# ADS1298.net
KiCad netlist of a schematic drawn in Altium Designer
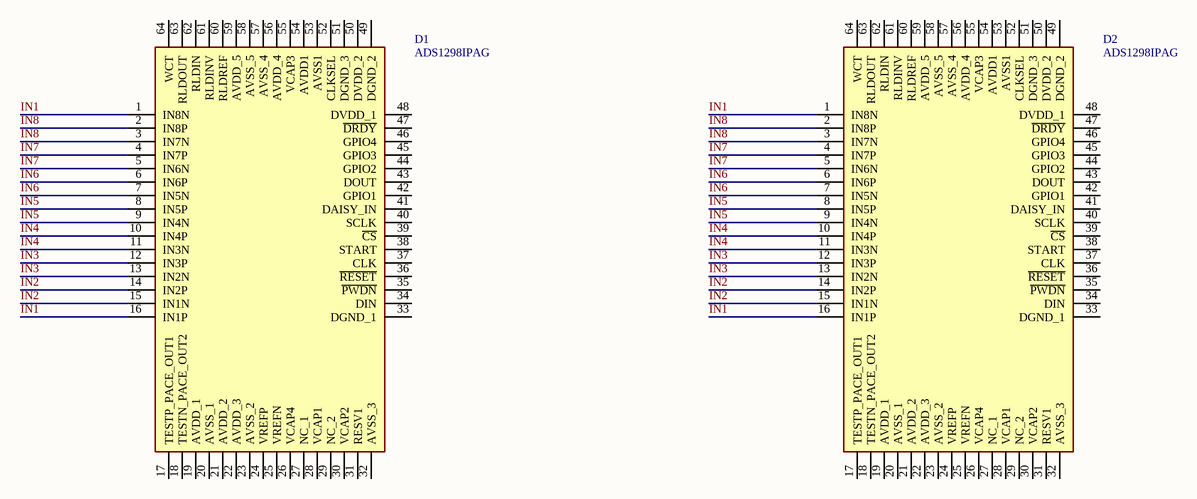
[diagram p0: ADS1298.SchDoc]

(export (version "E")
  (design (tool "Eeschema 10.0.6"))
  (components
    (comp (ref "D1")
      (value "ADS1298IPAG")
      (footprint "pcb_lib:QFP50P1200X1200X120-64N")
      (description "Integrated Circuit")
      (fields (field (name "MOUSER PART NUMBER") "595-ADS1298IPAG"))
      (libsource (lib "*") (part "ADS1298IPAG"))
    )
    (comp (ref "D2")
      (value "ADS1298IPAG")
      (footprint "pcb_lib:QFP50P1200X1200X120-64N")
      (description "Integrated Circuit")
      (fields (field (name "MOUSER PART NUMBER") "595-ADS1298IPAG"))
      (libsource (lib "*") (part "ADS1298IPAG"))
    )
  )
  (nets
    (net (code "1") (name "/IN1") (class "Default")
      (node (ref "D1") (pin "1") (pinfunction "IN8N_1") (pintype "passive"))
      (node (ref "D1") (pin "16") (pinfunction "IN1P_16") (pintype "passive"))
      (node (ref "D2") (pin "1") (pinfunction "IN8N_1") (pintype "passive"))
      (node (ref "D2") (pin "16") (pinfunction "IN1P_16") (pintype "passive"))
    )
    (net (code "2") (name "/IN2") (class "Default")
      (node (ref "D1") (pin "14") (pinfunction "IN2P_14") (pintype "passive"))
      (node (ref "D1") (pin "15") (pinfunction "IN1N_15") (pintype "passive"))
      (node (ref "D2") (pin "14") (pinfunction "IN2P_14") (pintype "passive"))
      (node (ref "D2") (pin "15") (pinfunction "IN1N_15") (pintype "passive"))
    )
    (net (code "3") (name "/IN3") (class "Default")
      (node (ref "D1") (pin "12") (pinfunction "IN3P_12") (pintype "passive"))
      (node (ref "D1") (pin "13") (pinfunction "IN2N_13") (pintype "passive"))
      (node (ref "D2") (pin "12") (pinfunction "IN3P_12") (pintype "passive"))
      (node (ref "D2") (pin "13") (pinfunction "IN2N_13") (pintype "passive"))
    )
    (net (code "4") (name "/IN4") (class "Default")
      (node (ref "D1") (pin "10") (pinfunction "IN4P_10") (pintype "passive"))
      (node (ref "D1") (pin "11") (pinfunction "IN3N_11") (pintype "passive"))
      (node (ref "D2") (pin "10") (pinfunction "IN4P_10") (pintype "passive"))
      (node (ref "D2") (pin "11") (pinfunction "IN3N_11") (pintype "passive"))
    )
    (net (code "5") (name "/IN5") (class "Default")
      (node (ref "D1") (pin "8") (pinfunction "IN5P_8") (pintype "passive"))
      (node (ref "D1") (pin "9") (pinfunction "IN4N_9") (pintype "passive"))
      (node (ref "D2") (pin "8") (pinfunction "IN5P_8") (pintype "passive"))
      (node (ref "D2") (pin "9") (pinfunction "IN4N_9") (pintype "passive"))
    )
    (net (code "6") (name "/IN6") (class "Default")
      (node (ref "D1") (pin "6") (pinfunction "IN6P_6") (pintype "passive"))
      (node (ref "D1") (pin "7") (pinfunction "IN5N_7") (pintype "passive"))
      (node (ref "D2") (pin "6") (pinfunction "IN6P_6") (pintype "passive"))
      (node (ref "D2") (pin "7") (pinfunction "IN5N_7") (pintype "passive"))
    )
    (net (code "7") (name "/IN7") (class "Default")
      (node (ref "D1") (pin "4") (pinfunction "IN7P_4") (pintype "passive"))
      (node (ref "D1") (pin "5") (pinfunction "IN6N_5") (pintype "passive"))
      (node (ref "D2") (pin "4") (pinfunction "IN7P_4") (pintype "passive"))
      (node (ref "D2") (pin "5") (pinfunction "IN6N_5") (pintype "passive"))
    )
    (net (code "8") (name "/IN8") (class "Default")
      (node (ref "D1") (pin "2") (pinfunction "IN8P_2") (pintype "passive"))
      (node (ref "D1") (pin "3") (pinfunction "IN7N_3") (pintype "passive"))
      (node (ref "D2") (pin "2") (pinfunction "IN8P_2") (pintype "passive"))
      (node (ref "D2") (pin "3") (pinfunction "IN7N_3") (pintype "passive"))
    )
    (net (code "9") (name "unconnected-(D1-AVDD1-Pad54)") (class "Default")
      (node (ref "D1") (pin "54") (pinfunction "AVDD1_54") (pintype "passive"))
    )
    (net (code "10") (name "unconnected-(D1-AVDD_1-Pad19)") (class "Default")
      (node (ref "D1") (pin "19") (pinfunction "AVDD_1_19") (pintype "passive"))
    )
    (net (code "11") (name "unconnected-(D1-AVDD_2-Pad21)") (class "Default")
      (node (ref "D1") (pin "21") (pinfunction "AVDD_2_21") (pintype "passive"))
    )
    (net (code "12") (name "unconnected-(D1-AVDD_3-Pad22)") (class "Default")
      (node (ref "D1") (pin "22") (pinfunction "AVDD_3_22") (pintype "passive"))
    )
    (net (code "13") (name "unconnected-(D1-AVDD_4-Pad56)") (class "Default")
      (node (ref "D1") (pin "56") (pinfunction "AVDD_4_56") (pintype "passive"))
    )
    (net (code "14") (name "unconnected-(D1-AVDD_5-Pad59)") (class "Default")
      (node (ref "D1") (pin "59") (pinfunction "AVDD_5_59") (pintype "passive"))
    )
    (net (code "15") (name "unconnected-(D1-AVSS1-Pad53)") (class "Default")
      (node (ref "D1") (pin "53") (pinfunction "AVSS1_53") (pintype "passive"))
    )
    (net (code "16") (name "unconnected-(D1-AVSS_1-Pad20)") (class "Default")
      (node (ref "D1") (pin "20") (pinfunction "AVSS_1_20") (pintype "passive"))
    )
    (net (code "17") (name "unconnected-(D1-AVSS_2-Pad23)") (class "Default")
      (node (ref "D1") (pin "23") (pinfunction "AVSS_2_23") (pintype "passive"))
    )
    (net (code "18") (name "unconnected-(D1-AVSS_3-Pad32)") (class "Default")
      (node (ref "D1") (pin "32") (pinfunction "AVSS_3_32") (pintype "passive"))
    )
    (net (code "19") (name "unconnected-(D1-AVSS_4-Pad57)") (class "Default")
      (node (ref "D1") (pin "57") (pinfunction "AVSS_4_57") (pintype "passive"))
    )
    (net (code "20") (name "unconnected-(D1-AVSS_5-Pad58)") (class "Default")
      (node (ref "D1") (pin "58") (pinfunction "AVSS_5_58") (pintype "passive"))
    )
    (net (code "21") (name "unconnected-(D1-CLK-Pad37)") (class "Default")
      (node (ref "D1") (pin "37") (pinfunction "CLK_37") (pintype "passive"))
    )
    (net (code "22") (name "unconnected-(D1-CLKSEL-Pad52)") (class "Default")
      (node (ref "D1") (pin "52") (pinfunction "CLKSEL_52") (pintype "passive"))
    )
    (net (code "23") (name "unconnected-(D1-DAISY_IN-Pad41)") (class "Default")
      (node (ref "D1") (pin "41") (pinfunction "DAISY_IN_41") (pintype "passive"))
    )
    (net (code "24") (name "unconnected-(D1-DGND_1-Pad33)") (class "Default")
      (node (ref "D1") (pin "33") (pinfunction "DGND_1_33") (pintype "passive"))
    )
    (net (code "25") (name "unconnected-(D1-DGND_2-Pad49)") (class "Default")
      (node (ref "D1") (pin "49") (pinfunction "DGND_2_49") (pintype "passive"))
    )
    (net (code "26") (name "unconnected-(D1-DGND_3-Pad51)") (class "Default")
      (node (ref "D1") (pin "51") (pinfunction "DGND_3_51") (pintype "passive"))
    )
    (net (code "27") (name "unconnected-(D1-DIN-Pad34)") (class "Default")
      (node (ref "D1") (pin "34") (pinfunction "DIN_34") (pintype "passive"))
    )
    (net (code "28") (name "unconnected-(D1-DOUT-Pad43)") (class "Default")
      (node (ref "D1") (pin "43") (pinfunction "DOUT_43") (pintype "passive"))
    )
    (net (code "29") (name "unconnected-(D1-DVDD_1-Pad48)") (class "Default")
      (node (ref "D1") (pin "48") (pinfunction "DVDD_1_48") (pintype "passive"))
    )
    (net (code "30") (name "unconnected-(D1-DVDD_2-Pad50)") (class "Default")
      (node (ref "D1") (pin "50") (pinfunction "DVDD_2_50") (pintype "passive"))
    )
    (net (code "31") (name "unconnected-(D1-GPIO1-Pad42)") (class "Default")
      (node (ref "D1") (pin "42") (pinfunction "GPIO1_42") (pintype "passive"))
    )
    (net (code "32") (name "unconnected-(D1-GPIO2-Pad44)") (class "Default")
      (node (ref "D1") (pin "44") (pinfunction "GPIO2_44") (pintype "passive"))
    )
    (net (code "33") (name "unconnected-(D1-GPIO3-Pad45)") (class "Default")
      (node (ref "D1") (pin "45") (pinfunction "GPIO3_45") (pintype "passive"))
    )
    (net (code "34") (name "unconnected-(D1-GPIO4-Pad46)") (class "Default")
      (node (ref "D1") (pin "46") (pinfunction "GPIO4_46") (pintype "passive"))
    )
    (net (code "35") (name "unconnected-(D1-NC_1-Pad27)") (class "Default")
      (node (ref "D1") (pin "27") (pinfunction "NC_1_27") (pintype "passive"))
    )
    (net (code "36") (name "unconnected-(D1-NC_2-Pad29)") (class "Default")
      (node (ref "D1") (pin "29") (pinfunction "NC_2_29") (pintype "passive"))
    )
    (net (code "37") (name "unconnected-(D1-RESV1-Pad31)") (class "Default")
      (node (ref "D1") (pin "31") (pinfunction "RESV1_31") (pintype "passive"))
    )
    (net (code "38") (name "unconnected-(D1-RLDIN-Pad62)") (class "Default")
      (node (ref "D1") (pin "62") (pinfunction "RLDIN_62") (pintype "passive"))
    )
    (net (code "39") (name "unconnected-(D1-RLDINV-Pad61)") (class "Default")
      (node (ref "D1") (pin "61") (pinfunction "RLDINV_61") (pintype "passive"))
    )
    (net (code "40") (name "unconnected-(D1-RLDOUT-Pad63)") (class "Default")
      (node (ref "D1") (pin "63") (pinfunction "RLDOUT_63") (pintype "passive"))
    )
    (net (code "41") (name "unconnected-(D1-RLDREF-Pad60)") (class "Default")
      (node (ref "D1") (pin "60") (pinfunction "RLDREF_60") (pintype "passive"))
    )
    (net (code "42") (name "unconnected-(D1-SCLK-Pad40)") (class "Default")
      (node (ref "D1") (pin "40") (pinfunction "SCLK_40") (pintype "passive"))
    )
    (net (code "43") (name "unconnected-(D1-START-Pad38)") (class "Default")
      (node (ref "D1") (pin "38") (pinfunction "START_38") (pintype "passive"))
    )
    (net (code "44") (name "unconnected-(D1-TESTN_PACE_OUT2-Pad18)") (class "Default")
      (node (ref "D1") (pin "18") (pinfunction "TESTN_PACE_OUT2_18") (pintype "passive"))
    )
    (net (code "45") (name "unconnected-(D1-TESTP_PACE_OUT1-Pad17)") (class "Default")
      (node (ref "D1") (pin "17") (pinfunction "TESTP_PACE_OUT1_17") (pintype "passive"))
    )
    (net (code "46") (name "unconnected-(D1-VCAP1-Pad28)") (class "Default")
      (node (ref "D1") (pin "28") (pinfunction "VCAP1_28") (pintype "passive"))
    )
    (net (code "47") (name "unconnected-(D1-VCAP2-Pad30)") (class "Default")
      (node (ref "D1") (pin "30") (pinfunction "VCAP2_30") (pintype "passive"))
    )
    (net (code "48") (name "unconnected-(D1-VCAP3-Pad55)") (class "Default")
      (node (ref "D1") (pin "55") (pinfunction "VCAP3_55") (pintype "passive"))
    )
    (net (code "49") (name "unconnected-(D1-VCAP4-Pad26)") (class "Default")
      (node (ref "D1") (pin "26") (pinfunction "VCAP4_26") (pintype "passive"))
    )
    (net (code "50") (name "unconnected-(D1-VREFN-Pad25)") (class "Default")
      (node (ref "D1") (pin "25") (pinfunction "VREFN_25") (pintype "passive"))
    )
    (net (code "51") (name "unconnected-(D1-VREFP-Pad24)") (class "Default")
      (node (ref "D1") (pin "24") (pinfunction "VREFP_24") (pintype "passive"))
    )
    (net (code "52") (name "unconnected-(D1-WCT-Pad64)") (class "Default")
      (node (ref "D1") (pin "64") (pinfunction "WCT_64") (pintype "passive"))
    )
    (net (code "53") (name "unconnected-(D1-~{CS}-Pad39)") (class "Default")
      (node (ref "D1") (pin "39") (pinfunction "~{CS}_39") (pintype "passive"))
    )
    (net (code "54") (name "unconnected-(D1-~{DRDY}-Pad47)") (class "Default")
      (node (ref "D1") (pin "47") (pinfunction "~{DRDY}_47") (pintype "passive"))
    )
    (net (code "55") (name "unconnected-(D1-~{PWDN}-Pad35)") (class "Default")
      (node (ref "D1") (pin "35") (pinfunction "~{PWDN}_35") (pintype "passive"))
    )
    (net (code "56") (name "unconnected-(D1-~{RESET}-Pad36)") (class "Default")
      (node (ref "D1") (pin "36") (pinfunction "~{RESET}_36") (pintype "passive"))
    )
    (net (code "57") (name "unconnected-(D2-AVDD1-Pad54)") (class "Default")
      (node (ref "D2") (pin "54") (pinfunction "AVDD1_54") (pintype "passive"))
    )
    (net (code "58") (name "unconnected-(D2-AVDD_1-Pad19)") (class "Default")
      (node (ref "D2") (pin "19") (pinfunction "AVDD_1_19") (pintype "passive"))
    )
    (net (code "59") (name "unconnected-(D2-AVDD_2-Pad21)") (class "Default")
      (node (ref "D2") (pin "21") (pinfunction "AVDD_2_21") (pintype "passive"))
    )
    (net (code "60") (name "unconnected-(D2-AVDD_3-Pad22)") (class "Default")
      (node (ref "D2") (pin "22") (pinfunction "AVDD_3_22") (pintype "passive"))
    )
    (net (code "61") (name "unconnected-(D2-AVDD_4-Pad56)") (class "Default")
      (node (ref "D2") (pin "56") (pinfunction "AVDD_4_56") (pintype "passive"))
    )
    (net (code "62") (name "unconnected-(D2-AVDD_5-Pad59)") (class "Default")
      (node (ref "D2") (pin "59") (pinfunction "AVDD_5_59") (pintype "passive"))
    )
    (net (code "63") (name "unconnected-(D2-AVSS1-Pad53)") (class "Default")
      (node (ref "D2") (pin "53") (pinfunction "AVSS1_53") (pintype "passive"))
    )
    (net (code "64") (name "unconnected-(D2-AVSS_1-Pad20)") (class "Default")
      (node (ref "D2") (pin "20") (pinfunction "AVSS_1_20") (pintype "passive"))
    )
    (net (code "65") (name "unconnected-(D2-AVSS_2-Pad23)") (class "Default")
      (node (ref "D2") (pin "23") (pinfunction "AVSS_2_23") (pintype "passive"))
    )
    (net (code "66") (name "unconnected-(D2-AVSS_3-Pad32)") (class "Default")
      (node (ref "D2") (pin "32") (pinfunction "AVSS_3_32") (pintype "passive"))
    )
    (net (code "67") (name "unconnected-(D2-AVSS_4-Pad57)") (class "Default")
      (node (ref "D2") (pin "57") (pinfunction "AVSS_4_57") (pintype "passive"))
    )
    (net (code "68") (name "unconnected-(D2-AVSS_5-Pad58)") (class "Default")
      (node (ref "D2") (pin "58") (pinfunction "AVSS_5_58") (pintype "passive"))
    )
    (net (code "69") (name "unconnected-(D2-CLK-Pad37)") (class "Default")
      (node (ref "D2") (pin "37") (pinfunction "CLK_37") (pintype "passive"))
    )
    (net (code "70") (name "unconnected-(D2-CLKSEL-Pad52)") (class "Default")
      (node (ref "D2") (pin "52") (pinfunction "CLKSEL_52") (pintype "passive"))
    )
    (net (code "71") (name "unconnected-(D2-DAISY_IN-Pad41)") (class "Default")
      (node (ref "D2") (pin "41") (pinfunction "DAISY_IN_41") (pintype "passive"))
    )
    (net (code "72") (name "unconnected-(D2-DGND_1-Pad33)") (class "Default")
      (node (ref "D2") (pin "33") (pinfunction "DGND_1_33") (pintype "passive"))
    )
    (net (code "73") (name "unconnected-(D2-DGND_2-Pad49)") (class "Default")
      (node (ref "D2") (pin "49") (pinfunction "DGND_2_49") (pintype "passive"))
    )
    (net (code "74") (name "unconnected-(D2-DGND_3-Pad51)") (class "Default")
      (node (ref "D2") (pin "51") (pinfunction "DGND_3_51") (pintype "passive"))
    )
    (net (code "75") (name "unconnected-(D2-DIN-Pad34)") (class "Default")
      (node (ref "D2") (pin "34") (pinfunction "DIN_34") (pintype "passive"))
    )
    (net (code "76") (name "unconnected-(D2-DOUT-Pad43)") (class "Default")
      (node (ref "D2") (pin "43") (pinfunction "DOUT_43") (pintype "passive"))
    )
    (net (code "77") (name "unconnected-(D2-DVDD_1-Pad48)") (class "Default")
      (node (ref "D2") (pin "48") (pinfunction "DVDD_1_48") (pintype "passive"))
    )
    (net (code "78") (name "unconnected-(D2-DVDD_2-Pad50)") (class "Default")
      (node (ref "D2") (pin "50") (pinfunction "DVDD_2_50") (pintype "passive"))
    )
    (net (code "79") (name "unconnected-(D2-GPIO1-Pad42)") (class "Default")
      (node (ref "D2") (pin "42") (pinfunction "GPIO1_42") (pintype "passive"))
    )
    (net (code "80") (name "unconnected-(D2-GPIO2-Pad44)") (class "Default")
      (node (ref "D2") (pin "44") (pinfunction "GPIO2_44") (pintype "passive"))
    )
    (net (code "81") (name "unconnected-(D2-GPIO3-Pad45)") (class "Default")
      (node (ref "D2") (pin "45") (pinfunction "GPIO3_45") (pintype "passive"))
    )
    (net (code "82") (name "unconnected-(D2-GPIO4-Pad46)") (class "Default")
      (node (ref "D2") (pin "46") (pinfunction "GPIO4_46") (pintype "passive"))
    )
    (net (code "83") (name "unconnected-(D2-NC_1-Pad27)") (class "Default")
      (node (ref "D2") (pin "27") (pinfunction "NC_1_27") (pintype "passive"))
    )
    (net (code "84") (name "unconnected-(D2-NC_2-Pad29)") (class "Default")
      (node (ref "D2") (pin "29") (pinfunction "NC_2_29") (pintype "passive"))
    )
    (net (code "85") (name "unconnected-(D2-RESV1-Pad31)") (class "Default")
      (node (ref "D2") (pin "31") (pinfunction "RESV1_31") (pintype "passive"))
    )
    (net (code "86") (name "unconnected-(D2-RLDIN-Pad62)") (class "Default")
      (node (ref "D2") (pin "62") (pinfunction "RLDIN_62") (pintype "passive"))
    )
    (net (code "87") (name "unconnected-(D2-RLDINV-Pad61)") (class "Default")
      (node (ref "D2") (pin "61") (pinfunction "RLDINV_61") (pintype "passive"))
    )
    (net (code "88") (name "unconnected-(D2-RLDOUT-Pad63)") (class "Default")
      (node (ref "D2") (pin "63") (pinfunction "RLDOUT_63") (pintype "passive"))
    )
    (net (code "89") (name "unconnected-(D2-RLDREF-Pad60)") (class "Default")
      (node (ref "D2") (pin "60") (pinfunction "RLDREF_60") (pintype "passive"))
    )
    (net (code "90") (name "unconnected-(D2-SCLK-Pad40)") (class "Default")
      (node (ref "D2") (pin "40") (pinfunction "SCLK_40") (pintype "passive"))
    )
    (net (code "91") (name "unconnected-(D2-START-Pad38)") (class "Default")
      (node (ref "D2") (pin "38") (pinfunction "START_38") (pintype "passive"))
    )
    (net (code "92") (name "unconnected-(D2-TESTN_PACE_OUT2-Pad18)") (class "Default")
      (node (ref "D2") (pin "18") (pinfunction "TESTN_PACE_OUT2_18") (pintype "passive"))
    )
    (net (code "93") (name "unconnected-(D2-TESTP_PACE_OUT1-Pad17)") (class "Default")
      (node (ref "D2") (pin "17") (pinfunction "TESTP_PACE_OUT1_17") (pintype "passive"))
    )
    (net (code "94") (name "unconnected-(D2-VCAP1-Pad28)") (class "Default")
      (node (ref "D2") (pin "28") (pinfunction "VCAP1_28") (pintype "passive"))
    )
    (net (code "95") (name "unconnected-(D2-VCAP2-Pad30)") (class "Default")
      (node (ref "D2") (pin "30") (pinfunction "VCAP2_30") (pintype "passive"))
    )
    (net (code "96") (name "unconnected-(D2-VCAP3-Pad55)") (class "Default")
      (node (ref "D2") (pin "55") (pinfunction "VCAP3_55") (pintype "passive"))
    )
    (net (code "97") (name "unconnected-(D2-VCAP4-Pad26)") (class "Default")
      (node (ref "D2") (pin "26") (pinfunction "VCAP4_26") (pintype "passive"))
    )
    (net (code "98") (name "unconnected-(D2-VREFN-Pad25)") (class "Default")
      (node (ref "D2") (pin "25") (pinfunction "VREFN_25") (pintype "passive"))
    )
    (net (code "99") (name "unconnected-(D2-VREFP-Pad24)") (class "Default")
      (node (ref "D2") (pin "24") (pinfunction "VREFP_24") (pintype "passive"))
    )
    (net (code "100") (name "unconnected-(D2-WCT-Pad64)") (class "Default")
      (node (ref "D2") (pin "64") (pinfunction "WCT_64") (pintype "passive"))
    )
    (net (code "101") (name "unconnected-(D2-~{CS}-Pad39)") (class "Default")
      (node (ref "D2") (pin "39") (pinfunction "~{CS}_39") (pintype "passive"))
    )
    (net (code "102") (name "unconnected-(D2-~{DRDY}-Pad47)") (class "Default")
      (node (ref "D2") (pin "47") (pinfunction "~{DRDY}_47") (pintype "passive"))
    )
    (net (code "103") (name "unconnected-(D2-~{PWDN}-Pad35)") (class "Default")
      (node (ref "D2") (pin "35") (pinfunction "~{PWDN}_35") (pintype "passive"))
    )
    (net (code "104") (name "unconnected-(D2-~{RESET}-Pad36)") (class "Default")
      (node (ref "D2") (pin "36") (pinfunction "~{RESET}_36") (pintype "passive"))
    )
  )
)
